# CAMGO.net
KiCad netlist of a schematic drawn in EAGLE
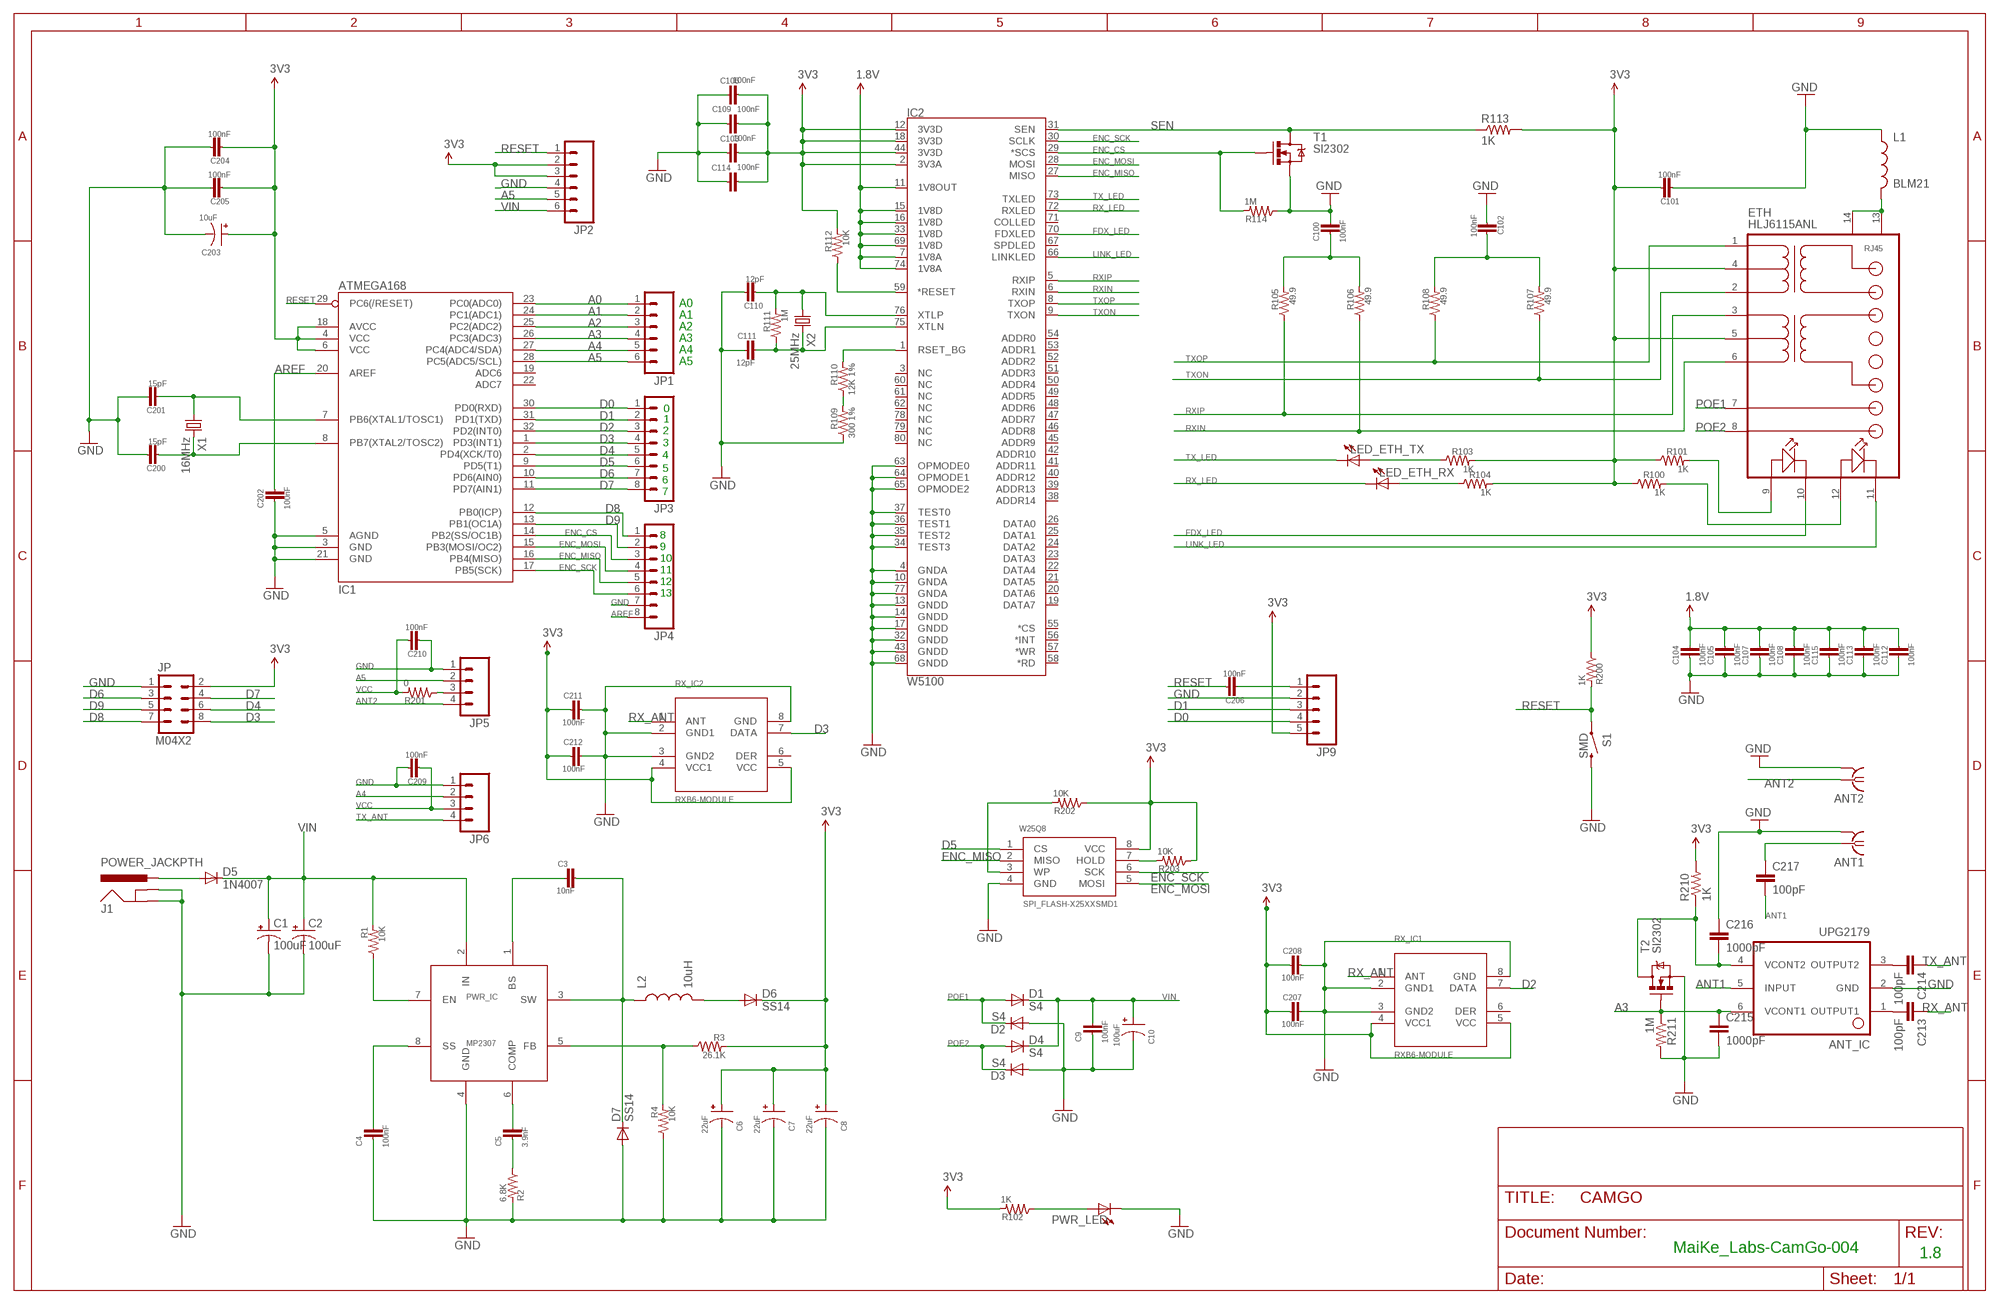
[diagram p0: schematic, sheet 1]

(export (version "E")
  (design (tool "Eeschema 10.0.6"))
  (components
    (comp (ref "ANT1")
      (value "SMA--KE")
      (footprint "eagle-import:SMA-KE")
      (libsource (lib "eagle-import") (part "SMA--KE"))
    )
    (comp (ref "ANT2")
      (value "SMA--KE")
      (footprint "eagle-import:SMA-KE")
      (libsource (lib "eagle-import") (part "SMA--KE"))
    )
    (comp (ref "ANT_IC")
      (value "UPG2179")
      (footprint "eagle-import:SOT363")
      (libsource (lib "eagle-import") (part "UPG2179"))
    )
    (comp (ref "C1")
      (value "100uF")
      (footprint "eagle-import:NIPPON_F80")
      (libsource (lib "eagle-import") (part "CAP_POLF80"))
    )
    (comp (ref "C2")
      (value "100uF")
      (footprint "eagle-import:NIPPON_F80")
      (libsource (lib "eagle-import") (part "CAP_POLF80"))
    )
    (comp (ref "C3")
      (value "10nF")
      (footprint "eagle-import:0603-CAP")
      (libsource (lib "eagle-import") (part "digital-toy_CAP0603-CAP"))
    )
    (comp (ref "C4")
      (value "100nF")
      (footprint "eagle-import:0603-CAP")
      (libsource (lib "eagle-import") (part "digital-toy_CAP0603-CAP"))
    )
    (comp (ref "C5")
      (value "3.9nF")
      (footprint "eagle-import:0603-CAP")
      (libsource (lib "eagle-import") (part "digital-toy_CAP0603-CAP"))
    )
    (comp (ref "C6")
      (value "22uF")
      (footprint "eagle-import:EIA3216")
      (libsource (lib "eagle-import") (part "digital-toy_CAP_POL1206"))
    )
    (comp (ref "C7")
      (value "22uF")
      (footprint "eagle-import:EIA3216")
      (libsource (lib "eagle-import") (part "digital-toy_CAP_POL1206"))
    )
    (comp (ref "C8")
      (value "22uF")
      (footprint "eagle-import:EIA3216")
      (libsource (lib "eagle-import") (part "digital-toy_CAP_POL1206"))
    )
    (comp (ref "C9")
      (value "100nF")
      (footprint "eagle-import:0603-CAP")
      (libsource (lib "eagle-import") (part "digital-toy_CAP0603-CAP"))
    )
    (comp (ref "C10")
      (value "100uF")
      (footprint "eagle-import:NIPPON_F80")
      (libsource (lib "eagle-import") (part "digital-toy_CAP_POLF80"))
    )
    (comp (ref "C100")
      (value "100nF")
      (footprint "eagle-import:0603-CAP")
      (libsource (lib "eagle-import") (part "digital-toy_CAP0603-CAP"))
    )
    (comp (ref "C101")
      (value "100nF")
      (footprint "eagle-import:0603-CAP")
      (libsource (lib "eagle-import") (part "digital-toy_CAP0603-CAP"))
    )
    (comp (ref "C102")
      (value "100nF")
      (footprint "eagle-import:0603-CAP")
      (libsource (lib "eagle-import") (part "digital-toy_CAP0603-CAP"))
    )
    (comp (ref "C103")
      (value "100nF")
      (footprint "eagle-import:0603-CAP")
      (libsource (lib "eagle-import") (part "digital-toy_CAP0603-CAP"))
    )
    (comp (ref "C104")
      (value "100nF")
      (footprint "eagle-import:0603-CAP")
      (libsource (lib "eagle-import") (part "digital-toy_CAP0603-CAP"))
    )
    (comp (ref "C105")
      (value "100nF")
      (footprint "eagle-import:0603-CAP")
      (libsource (lib "eagle-import") (part "digital-toy_CAP0603-CAP"))
    )
    (comp (ref "C106")
      (value "100nF")
      (footprint "eagle-import:0603-CAP")
      (libsource (lib "eagle-import") (part "digital-toy_CAP0603-CAP"))
    )
    (comp (ref "C107")
      (value "100nF")
      (footprint "eagle-import:0603-CAP")
      (libsource (lib "eagle-import") (part "digital-toy_CAP0603-CAP"))
    )
    (comp (ref "C108")
      (value "100nF")
      (footprint "eagle-import:0603-CAP")
      (libsource (lib "eagle-import") (part "digital-toy_CAP0603-CAP"))
    )
    (comp (ref "C109")
      (value "100nF")
      (footprint "eagle-import:0603-CAP")
      (libsource (lib "eagle-import") (part "digital-toy_CAP0603-CAP"))
    )
    (comp (ref "C110")
      (value "12pF")
      (footprint "eagle-import:0603-CAP")
      (libsource (lib "eagle-import") (part "digital-toy_CAP0603-CAP"))
    )
    (comp (ref "C111")
      (value "12pF")
      (footprint "eagle-import:0603-CAP")
      (libsource (lib "eagle-import") (part "digital-toy_CAP0603-CAP"))
    )
    (comp (ref "C112")
      (value "100nF")
      (footprint "eagle-import:0603-CAP")
      (libsource (lib "eagle-import") (part "digital-toy_CAP0603-CAP"))
    )
    (comp (ref "C113")
      (value "100nF")
      (footprint "eagle-import:0603-CAP")
      (libsource (lib "eagle-import") (part "digital-toy_CAP0603-CAP"))
    )
    (comp (ref "C114")
      (value "100nF")
      (footprint "eagle-import:0603-CAP")
      (libsource (lib "eagle-import") (part "digital-toy_CAP0603-CAP"))
    )
    (comp (ref "C115")
      (value "100nF")
      (footprint "eagle-import:0603-CAP")
      (libsource (lib "eagle-import") (part "digital-toy_CAP0603-CAP"))
    )
    (comp (ref "C200")
      (value "15pF")
      (footprint "eagle-import:0603-CAP")
      (libsource (lib "eagle-import") (part "digital-toy_CAP0603-CAP"))
    )
    (comp (ref "C201")
      (value "15pF")
      (footprint "eagle-import:0603-CAP")
      (libsource (lib "eagle-import") (part "digital-toy_CAP0603-CAP"))
    )
    (comp (ref "C202")
      (value "100nF")
      (footprint "eagle-import:0603-CAP")
      (libsource (lib "eagle-import") (part "digital-toy_CAP0603-CAP"))
    )
    (comp (ref "C203")
      (value "10uF")
      (footprint "eagle-import:EIA3216")
      (libsource (lib "eagle-import") (part "digital-toy_CAP_POL1206"))
    )
    (comp (ref "C204")
      (value "100nF")
      (footprint "eagle-import:0603-CAP")
      (libsource (lib "eagle-import") (part "digital-toy_CAP0603-CAP"))
    )
    (comp (ref "C205")
      (value "100nF")
      (footprint "eagle-import:0603-CAP")
      (libsource (lib "eagle-import") (part "digital-toy_CAP0603-CAP"))
    )
    (comp (ref "C206")
      (value "100nF")
      (footprint "eagle-import:0603-CAP")
      (libsource (lib "eagle-import") (part "digital-toy_CAP0603-CAP"))
    )
    (comp (ref "C207")
      (value "100nF")
      (footprint "eagle-import:0603-CAP")
      (libsource (lib "eagle-import") (part "digital-toy_CAP0603-CAP"))
    )
    (comp (ref "C208")
      (value "100nF")
      (footprint "eagle-import:0603-CAP")
      (libsource (lib "eagle-import") (part "digital-toy_CAP0603-CAP"))
    )
    (comp (ref "C209")
      (value "100nF")
      (footprint "eagle-import:0603-CAP")
      (libsource (lib "eagle-import") (part "digital-toy_CAP0603-CAP"))
    )
    (comp (ref "C210")
      (value "100nF")
      (footprint "eagle-import:0603-CAP")
      (libsource (lib "eagle-import") (part "digital-toy_CAP0603-CAP"))
    )
    (comp (ref "C211")
      (value "100nF")
      (footprint "eagle-import:0603-CAP")
      (libsource (lib "eagle-import") (part "digital-toy_CAP0603-CAP"))
    )
    (comp (ref "C212")
      (value "100nF")
      (footprint "eagle-import:0603-CAP")
      (libsource (lib "eagle-import") (part "digital-toy_CAP0603-CAP"))
    )
    (comp (ref "C213")
      (value "100pF")
      (footprint "eagle-import:0603-CAP")
      (libsource (lib "eagle-import") (part "CAP0603-CAP"))
    )
    (comp (ref "C214")
      (value "100pF")
      (footprint "eagle-import:0603-CAP")
      (libsource (lib "eagle-import") (part "CAP0603-CAP"))
    )
    (comp (ref "C215")
      (value "1000pF")
      (footprint "eagle-import:0603-CAP")
      (libsource (lib "eagle-import") (part "CAP0603-CAP"))
    )
    (comp (ref "C216")
      (value "1000pF")
      (footprint "eagle-import:0603-CAP")
      (libsource (lib "eagle-import") (part "CAP0603-CAP"))
    )
    (comp (ref "C217")
      (value "100pF")
      (footprint "eagle-import:0603-CAP")
      (libsource (lib "eagle-import") (part "CAP0603-CAP"))
    )
    (comp (ref "D1")
      (value "S4")
      (footprint "eagle-import:SOD-323")
      (libsource (lib "eagle-import") (part "ehl_DIODESOD"))
    )
    (comp (ref "D2")
      (value "S4")
      (footprint "eagle-import:SOD-323")
      (libsource (lib "eagle-import") (part "ehl_DIODESOD"))
    )
    (comp (ref "D3")
      (value "S4")
      (footprint "eagle-import:SOD-323")
      (libsource (lib "eagle-import") (part "ehl_DIODESOD"))
    )
    (comp (ref "D4")
      (value "S4")
      (footprint "eagle-import:SOD-323")
      (libsource (lib "eagle-import") (part "ehl_DIODESOD"))
    )
    (comp (ref "D5")
      (value "1N4007")
      (footprint "eagle-import:SMB-DIODE")
      (libsource (lib "eagle-import") (part "DIODESMB"))
    )
    (comp (ref "D6")
      (value "SS14")
      (footprint "eagle-import:SOD-323")
      (libsource (lib "eagle-import") (part "DIODESOD"))
    )
    (comp (ref "D7")
      (value "SS14")
      (footprint "eagle-import:SOD-323")
      (libsource (lib "eagle-import") (part "DIODESOD"))
    )
    (comp (ref "ETH")
      (value "HLJ6115ANL")
      (footprint "eagle-import:HR911105A")
      (libsource (lib "eagle-import") (part "HLJ6115ANL"))
    )
    (comp (ref "IC1")
      (value "ATMEGA168")
      (footprint "eagle-import:TQFP32-08")
      (libsource (lib "eagle-import") (part "ATMEGA168"))
    )
    (comp (ref "IC2")
      (value "W5100")
      (footprint "eagle-import:LQFP-80")
      (libsource (lib "eagle-import") (part "W5100"))
    )
    (comp (ref "J1")
      (value "POWER_JACKPTH")
      (footprint "eagle-import:POWER_JACK_PTH")
      (libsource (lib "eagle-import") (part "POWER_JACKPTH"))
    )
    (comp (ref "JP")
      (value "M04X2")
      (footprint "eagle-import:2X4")
      (libsource (lib "eagle-import") (part "M04X2"))
    )
    (comp (ref "JP1")
      (value "M06SIP")
      (footprint "eagle-import:1X06")
      (libsource (lib "eagle-import") (part "M06SIP"))
    )
    (comp (ref "JP2")
      (value "M06SIP")
      (footprint "eagle-import:1X06")
      (libsource (lib "eagle-import") (part "M06SIP"))
    )
    (comp (ref "JP3")
      (value "M081X08")
      (footprint "eagle-import:1X08")
      (libsource (lib "eagle-import") (part "M081X08"))
    )
    (comp (ref "JP4")
      (value "M081X08")
      (footprint "eagle-import:1X08")
      (libsource (lib "eagle-import") (part "M081X08"))
    )
    (comp (ref "JP5")
      (value "M04PTH")
      (footprint "eagle-import:1X04")
      (libsource (lib "eagle-import") (part "M04PTH"))
    )
    (comp (ref "JP6")
      (value "M04PTH")
      (footprint "eagle-import:1X04")
      (libsource (lib "eagle-import") (part "M04PTH"))
    )
    (comp (ref "JP9")
      (value "M05PTH")
      (footprint "eagle-import:1X05")
      (libsource (lib "eagle-import") (part "M05PTH"))
    )
    (comp (ref "L1")
      (value "BLM21")
      (footprint "eagle-import:0805")
      (libsource (lib "eagle-import") (part "INDUCTOR0805"))
    )
    (comp (ref "L2")
      (value "10uH")
      (footprint "eagle-import:CR54")
      (libsource (lib "eagle-import") (part "INDUCTORCR54"))
    )
    (comp (ref "LED_ETH_RX")
      (value "LED0603")
      (footprint "eagle-import:LED-0603")
      (libsource (lib "eagle-import") (part "LED0603"))
    )
    (comp (ref "LED_ETH_TX")
      (value "LED0603")
      (footprint "eagle-import:LED-0603")
      (libsource (lib "eagle-import") (part "LED0603"))
    )
    (comp (ref "PWR_IC")
      (value "MP2307")
      (footprint "eagle-import:SOIC8")
      (libsource (lib "eagle-import") (part "MP2302"))
    )
    (comp (ref "PWR_LED")
      (value "LED0603")
      (footprint "eagle-import:LED-0603")
      (libsource (lib "eagle-import") (part "LED0603"))
    )
    (comp (ref "R1")
      (value "10K")
      (footprint "eagle-import:0603-RES")
      (libsource (lib "eagle-import") (part "digital-toy_RESISTOR0603-RES"))
    )
    (comp (ref "R2")
      (value "6.8K")
      (footprint "eagle-import:0603-RES")
      (libsource (lib "eagle-import") (part "digital-toy_RESISTOR0603-RES"))
    )
    (comp (ref "R3")
      (value "26.1K")
      (footprint "eagle-import:0603-RES")
      (libsource (lib "eagle-import") (part "digital-toy_RESISTOR0603-RES"))
    )
    (comp (ref "R4")
      (value "10K")
      (footprint "eagle-import:0603-RES")
      (libsource (lib "eagle-import") (part "digital-toy_RESISTOR0603-RES"))
    )
    (comp (ref "R100")
      (value "1K")
      (footprint "eagle-import:0603-RES")
      (libsource (lib "eagle-import") (part "digital-toy_RESISTOR0603-RES"))
    )
    (comp (ref "R101")
      (value "1K")
      (footprint "eagle-import:0603-RES")
      (libsource (lib "eagle-import") (part "digital-toy_RESISTOR0603-RES"))
    )
    (comp (ref "R102")
      (value "1K")
      (footprint "eagle-import:0603-RES")
      (libsource (lib "eagle-import") (part "digital-toy_RESISTOR0603-RES"))
    )
    (comp (ref "R103")
      (value "1K")
      (footprint "eagle-import:0603-RES")
      (libsource (lib "eagle-import") (part "digital-toy_RESISTOR0603-RES"))
    )
    (comp (ref "R104")
      (value "1K")
      (footprint "eagle-import:0603-RES")
      (libsource (lib "eagle-import") (part "digital-toy_RESISTOR0603-RES"))
    )
    (comp (ref "R105")
      (value "49.9")
      (footprint "eagle-import:0603-RES")
      (libsource (lib "eagle-import") (part "digital-toy_RESISTOR0603-RES"))
    )
    (comp (ref "R106")
      (value "49.9")
      (footprint "eagle-import:0603-RES")
      (libsource (lib "eagle-import") (part "digital-toy_RESISTOR0603-RES"))
    )
    (comp (ref "R107")
      (value "49.9")
      (footprint "eagle-import:0603-RES")
      (libsource (lib "eagle-import") (part "digital-toy_RESISTOR0603-RES"))
    )
    (comp (ref "R108")
      (value "49.9")
      (footprint "eagle-import:0603-RES")
      (libsource (lib "eagle-import") (part "digital-toy_RESISTOR0603-RES"))
    )
    (comp (ref "R109")
      (value "300 1%")
      (footprint "eagle-import:0603-RES")
      (libsource (lib "eagle-import") (part "digital-toy_RESISTOR0603-RES"))
    )
    (comp (ref "R110")
      (value "12K 1%")
      (footprint "eagle-import:0603-RES")
      (libsource (lib "eagle-import") (part "digital-toy_RESISTOR0603-RES"))
    )
    (comp (ref "R111")
      (value "1M")
      (footprint "eagle-import:0603-RES")
      (libsource (lib "eagle-import") (part "digital-toy_RESISTOR0603-RES"))
    )
    (comp (ref "R112")
      (value "10K")
      (footprint "eagle-import:0603-RES")
      (libsource (lib "eagle-import") (part "digital-toy_RESISTOR0603-RES"))
    )
    (comp (ref "R113")
      (value "1K")
      (footprint "eagle-import:0603-RES")
      (libsource (lib "eagle-import") (part "RESISTOR0603-RES"))
    )
    (comp (ref "R114")
      (value "1M")
      (footprint "eagle-import:0603-RES")
      (libsource (lib "eagle-import") (part "digital-toy_RESISTOR0603-RES"))
    )
    (comp (ref "R200")
      (value "1K")
      (footprint "eagle-import:0603-RES")
      (libsource (lib "eagle-import") (part "digital-toy_RESISTOR0603-RES"))
    )
    (comp (ref "R201")
      (value "0")
      (footprint "eagle-import:0603-RES")
      (libsource (lib "eagle-import") (part "digital-toy_RESISTOR0603-RES"))
    )
    (comp (ref "R202")
      (value "10K")
      (footprint "eagle-import:0603-RES")
      (libsource (lib "eagle-import") (part "digital-toy_RESISTOR0603-RES"))
    )
    (comp (ref "R203")
      (value "10K")
      (footprint "eagle-import:0603-RES")
      (libsource (lib "eagle-import") (part "digital-toy_RESISTOR0603-RES"))
    )
    (comp (ref "R210")
      (value "1K")
      (footprint "eagle-import:0603-RES")
      (libsource (lib "eagle-import") (part "RESISTOR0603-RES"))
    )
    (comp (ref "R211")
      (value "1M")
      (footprint "eagle-import:0603-RES")
      (libsource (lib "eagle-import") (part "RESISTOR0603-RES"))
    )
    (comp (ref "RX_IC1")
      (value "RXB6-MODULE")
      (footprint "eagle-import:RXB6-MODULE")
      (libsource (lib "eagle-import") (part "RXB6-MODULE"))
    )
    (comp (ref "RX_IC2")
      (value "RXB6-MODULE")
      (footprint "eagle-import:RXB6-MODULE")
      (libsource (lib "eagle-import") (part "RXB6-MODULE"))
    )
    (comp (ref "S1")
      (value "SMD")
      (footprint "eagle-import:TACTILE-SWITCH-1101NE")
      (libsource (lib "eagle-import") (part "SWITCH-MOMENTARY-2-SMD-1101NE"))
    )
    (comp (ref "T1")
      (value "SI2302")
      (footprint "eagle-import:SOT23-3")
      (libsource (lib "eagle-import") (part "-MOSFET-N-SMD"))
    )
    (comp (ref "T2")
      (value "SI2302")
      (footprint "eagle-import:SOT23-3")
      (libsource (lib "eagle-import") (part "-MOSFET-N-SMD"))
    )
    (comp (ref "W25Q8")
      (value "SPI_FLASH-X25XXSMD1")
      (footprint "eagle-import:SO08-EIAJ")
      (libsource (lib "eagle-import") (part "SPI_FLASH-X25XXSMD1"))
    )
    (comp (ref "X1")
      (value "16MHz")
      (footprint "eagle-import:HC49US")
      (libsource (lib "eagle-import") (part "CRYSTALHC49US"))
    )
    (comp (ref "X2")
      (value "25MHz")
      (footprint "eagle-import:HC49US")
      (libsource (lib "eagle-import") (part "CRYSTALHC49US"))
    )
  )
  (nets
    (net (code "1") (name "/A0") (class "Default")
      (node (ref "IC1") (pin "23") (pinfunction "PC0(ADC0)_23") (pintype "bidirectional"))
      (node (ref "JP1") (pin "1") (pinfunction "1_1") (pintype "passive"))
    )
    (net (code "2") (name "/A1") (class "Default")
      (node (ref "IC1") (pin "24") (pinfunction "PC1(ADC1)_24") (pintype "bidirectional"))
      (node (ref "JP1") (pin "2") (pinfunction "2_2") (pintype "passive"))
    )
    (net (code "3") (name "/A2") (class "Default")
      (node (ref "IC1") (pin "25") (pinfunction "PC2(ADC2)_25") (pintype "bidirectional"))
      (node (ref "JP1") (pin "3") (pinfunction "3_3") (pintype "passive"))
    )
    (net (code "4") (name "/A3") (class "Default")
      (node (ref "ANT_IC") (pin "6") (pinfunction "VCONT1_6") (pintype "bidirectional"))
      (node (ref "C215") (pin "1") (pinfunction "1_1") (pintype "passive"))
      (node (ref "IC1") (pin "26") (pinfunction "PC3(ADC3)_26") (pintype "bidirectional"))
      (node (ref "JP1") (pin "4") (pinfunction "4_4") (pintype "passive"))
      (node (ref "R211") (pin "1") (pinfunction "1_1") (pintype "passive"))
      (node (ref "T2") (pin "1") (pinfunction "G_1") (pintype "passive"))
    )
    (net (code "5") (name "/A4") (class "Default")
      (node (ref "IC1") (pin "27") (pinfunction "PC4(ADC4/SDA)_27") (pintype "bidirectional"))
      (node (ref "JP1") (pin "5") (pinfunction "5_5") (pintype "passive"))
      (node (ref "JP6") (pin "2") (pinfunction "2_2") (pintype "passive"))
    )
    (net (code "6") (name "/A5") (class "Default")
      (node (ref "IC1") (pin "28") (pinfunction "PC5(ADC5/SCL)_28") (pintype "bidirectional"))
      (node (ref "JP1") (pin "6") (pinfunction "6_6") (pintype "passive"))
      (node (ref "JP2") (pin "5") (pinfunction "5_5") (pintype "passive"))
      (node (ref "JP5") (pin "2") (pinfunction "2_2") (pintype "passive"))
    )
    (net (code "7") (name "/ANT1") (class "Default")
      (node (ref "ANT_IC") (pin "5") (pinfunction "INPUT_5") (pintype "bidirectional"))
      (node (ref "C217") (pin "2") (pinfunction "2_2") (pintype "passive"))
    )
    (net (code "8") (name "/ANT2") (class "Default")
      (node (ref "ANT2") (pin "1") (pinfunction "1_1") (pintype "passive"))
      (node (ref "JP5") (pin "4") (pinfunction "4_4") (pintype "passive"))
    )
    (net (code "9") (name "/AREF") (class "Default")
      (node (ref "C202") (pin "1") (pinfunction "1_1") (pintype "passive"))
      (node (ref "IC1") (pin "20") (pinfunction "AREF_20") (pintype "bidirectional"))
      (node (ref "JP4") (pin "8") (pinfunction "8_8") (pintype "passive"))
    )
    (net (code "10") (name "/D0") (class "Default")
      (node (ref "IC1") (pin "30") (pinfunction "PD0(RXD)_30") (pintype "bidirectional"))
      (node (ref "JP3") (pin "1") (pinfunction "1_1") (pintype "passive"))
      (node (ref "JP9") (pin "4") (pinfunction "4_4") (pintype "passive"))
    )
    (net (code "11") (name "/D1") (class "Default")
      (node (ref "IC1") (pin "31") (pinfunction "PD1(TXD)_31") (pintype "bidirectional"))
      (node (ref "JP3") (pin "2") (pinfunction "2_2") (pintype "passive"))
      (node (ref "JP9") (pin "3") (pinfunction "3_3") (pintype "passive"))
    )
    (net (code "12") (name "/D2") (class "Default")
      (node (ref "IC1") (pin "32") (pinfunction "PD2(INT0)_32") (pintype "bidirectional"))
      (node (ref "JP3") (pin "3") (pinfunction "3_3") (pintype "passive"))
      (node (ref "RX_IC1") (pin "7") (pinfunction "DATA_7") (pintype "bidirectional"))
    )
    (net (code "13") (name "/D3") (class "Default")
      (node (ref "IC1") (pin "1") (pinfunction "PD3(INT1)_1") (pintype "bidirectional"))
      (node (ref "JP") (pin "8") (pinfunction "8_8") (pintype "passive"))
      (node (ref "JP3") (pin "4") (pinfunction "4_4") (pintype "passive"))
      (node (ref "RX_IC2") (pin "7") (pinfunction "DATA_7") (pintype "bidirectional"))
    )
    (net (code "14") (name "/D4") (class "Default")
      (node (ref "IC1") (pin "2") (pinfunction "PD4(XCK/T0)_2") (pintype "bidirectional"))
      (node (ref "JP") (pin "6") (pinfunction "6_6") (pintype "passive"))
      (node (ref "JP3") (pin "5") (pinfunction "5_5") (pintype "passive"))
    )
    (net (code "15") (name "/D5") (class "Default")
      (node (ref "IC1") (pin "9") (pinfunction "PD5(T1)_9") (pintype "bidirectional"))
      (node (ref "JP3") (pin "6") (pinfunction "6_6") (pintype "passive"))
      (node (ref "W25Q8") (pin "1") (pinfunction "CS_1") (pintype "bidirectional"))
    )
    (net (code "16") (name "/D6") (class "Default")
      (node (ref "IC1") (pin "10") (pinfunction "PD6(AIN0)_10") (pintype "bidirectional"))
      (node (ref "JP") (pin "3") (pinfunction "3_3") (pintype "passive"))
      (node (ref "JP3") (pin "7") (pinfunction "7_7") (pintype "passive"))
    )
    (net (code "17") (name "/D7") (class "Default")
      (node (ref "IC1") (pin "11") (pinfunction "PD7(AIN1)_11") (pintype "bidirectional"))
      (node (ref "JP") (pin "4") (pinfunction "4_4") (pintype "passive"))
      (node (ref "JP3") (pin "8") (pinfunction "8_8") (pintype "passive"))
    )
    (net (code "18") (name "/D8") (class "Default")
      (node (ref "IC1") (pin "12") (pinfunction "PB0(ICP)_12") (pintype "bidirectional"))
      (node (ref "JP") (pin "7") (pinfunction "7_7") (pintype "passive"))
      (node (ref "JP4") (pin "1") (pinfunction "1_1") (pintype "passive"))
    )
    (net (code "19") (name "/D9") (class "Default")
      (node (ref "IC1") (pin "13") (pinfunction "PB1(OC1A)_13") (pintype "bidirectional"))
      (node (ref "JP") (pin "5") (pinfunction "5_5") (pintype "passive"))
      (node (ref "JP4") (pin "2") (pinfunction "2_2") (pintype "passive"))
    )
    (net (code "20") (name "/ENC_CS") (class "Default")
      (node (ref "IC1") (pin "14") (pinfunction "PB2(SS/OC1B)_14") (pintype "bidirectional"))
      (node (ref "IC2") (pin "29") (pinfunction "*SCS_29") (pintype "bidirectional"))
      (node (ref "JP4") (pin "3") (pinfunction "3_3") (pintype "passive"))
      (node (ref "R114") (pin "2") (pinfunction "2_2") (pintype "passive"))
      (node (ref "T1") (pin "1") (pinfunction "G_1") (pintype "passive"))
    )
    (net (code "21") (name "/ENC_MISO") (class "Default")
      (node (ref "IC1") (pin "16") (pinfunction "PB4(MISO)_16") (pintype "bidirectional"))
      (node (ref "IC2") (pin "27") (pinfunction "MISO_27") (pintype "bidirectional"))
      (node (ref "JP4") (pin "5") (pinfunction "5_5") (pintype "passive"))
      (node (ref "W25Q8") (pin "2") (pinfunction "MISO_2") (pintype "bidirectional"))
    )
    (net (code "22") (name "/ENC_MOSI") (class "Default")
      (node (ref "IC1") (pin "15") (pinfunction "PB3(MOSI/OC2)_15") (pintype "bidirectional"))
      (node (ref "IC2") (pin "28") (pinfunction "MOSI_28") (pintype "bidirectional"))
      (node (ref "JP4") (pin "4") (pinfunction "4_4") (pintype "passive"))
      (node (ref "W25Q8") (pin "5") (pinfunction "MOSI_5") (pintype "bidirectional"))
    )
    (net (code "23") (name "/ENC_SCK") (class "Default")
      (node (ref "IC1") (pin "17") (pinfunction "PB5(SCK)_17") (pintype "bidirectional"))
      (node (ref "IC2") (pin "30") (pinfunction "SCLK_30") (pintype "bidirectional"))
      (node (ref "JP4") (pin "6") (pinfunction "6_6") (pintype "passive"))
      (node (ref "W25Q8") (pin "6") (pinfunction "SCK_6") (pintype "bidirectional"))
    )
    (net (code "24") (name "/FDX_LED") (class "Default")
      (node (ref "ETH") (pin "10") (pinfunction "10_10") (pintype "bidirectional"))
      (node (ref "IC2") (pin "70") (pinfunction "FDXLED_70") (pintype "bidirectional"))
    )
    (net (code "25") (name "/LINK_LED") (class "Default")
      (node (ref "ETH") (pin "11") (pinfunction "11_11") (pintype "bidirectional"))
      (node (ref "IC2") (pin "66") (pinfunction "LINKLED_66") (pintype "bidirectional"))
    )
    (net (code "26") (name "/POE1") (class "Default")
      (node (ref "D1") (pin "2") (pinfunction "A_2") (pintype "passive"))
      (node (ref "D2") (pin "1") (pinfunction "C_1") (pintype "passive"))
      (node (ref "ETH") (pin "7") (pinfunction "7_7") (pintype "bidirectional"))
    )
    (net (code "27") (name "/POE2") (class "Default")
      (node (ref "D3") (pin "1") (pinfunction "C_1") (pintype "passive"))
      (node (ref "D4") (pin "2") (pinfunction "A_2") (pintype "passive"))
      (node (ref "ETH") (pin "8") (pinfunction "8_8") (pintype "bidirectional"))
    )
    (net (code "28") (name "/RESET") (class "Default")
      (node (ref "C206") (pin "1") (pinfunction "1_1") (pintype "passive"))
      (node (ref "IC1") (pin "29") (pinfunction "PC6(/RESET)_29") (pintype "bidirectional"))
      (node (ref "IC2") (pin "59") (pinfunction "*RESET_59") (pintype "bidirectional"))
      (node (ref "JP2") (pin "1") (pinfunction "1_1") (pintype "passive"))
      (node (ref "R112") (pin "1") (pinfunction "1_1") (pintype "passive"))
      (node (ref "R200") (pin "2") (pinfunction "2_2") (pintype "passive"))
      (node (ref "S1") (pin "P$1") (pinfunction "1_P$1") (pintype "passive"))
    )
    (net (code "29") (name "/RXIN") (class "Default")
      (node (ref "ETH") (pin "6") (pinfunction "6_6") (pintype "bidirectional"))
      (node (ref "IC2") (pin "6") (pinfunction "RXIN_6") (pintype "bidirectional"))
      (node (ref "R106") (pin "1") (pinfunction "1_1") (pintype "passive"))
    )
    (net (code "30") (name "/RXIP") (class "Default")
      (node (ref "ETH") (pin "3") (pinfunction "3_3") (pintype "bidirectional"))
      (node (ref "IC2") (pin "5") (pinfunction "RXIP_5") (pintype "bidirectional"))
      (node (ref "R105") (pin "1") (pinfunction "1_1") (pintype "passive"))
    )
    (net (code "31") (name "/RX_ANT") (class "Default")
      (node (ref "C213") (pin "1") (pinfunction "1_1") (pintype "passive"))
      (node (ref "RX_IC1") (pin "1") (pinfunction "ANT_1") (pintype "bidirectional"))
      (node (ref "RX_IC2") (pin "1") (pinfunction "ANT_1") (pintype "bidirectional"))
    )
    (net (code "32") (name "/RX_LED") (class "Default")
      (node (ref "IC2") (pin "72") (pinfunction "RXLED_72") (pintype "bidirectional"))
      (node (ref "LED_ETH_RX") (pin "C") (pinfunction "C_C") (pintype "passive"))
    )
    (net (code "33") (name "/SEN") (class "Default")
      (node (ref "IC2") (pin "31") (pinfunction "SEN_31") (pintype "bidirectional"))
      (node (ref "R113") (pin "1") (pinfunction "1_1") (pintype "passive"))
      (node (ref "T1") (pin "3") (pinfunction "D_3") (pintype "passive"))
    )
    (net (code "34") (name "/TXON") (class "Default")
      (node (ref "ETH") (pin "2") (pinfunction "2_2") (pintype "bidirectional"))
      (node (ref "IC2") (pin "9") (pinfunction "TXON_9") (pintype "bidirectional"))
      (node (ref "R107") (pin "1") (pinfunction "1_1") (pintype "passive"))
    )
    (net (code "35") (name "/TXOP") (class "Default")
      (node (ref "ETH") (pin "1") (pinfunction "1_1") (pintype "bidirectional"))
      (node (ref "IC2") (pin "8") (pinfunction "TXOP_8") (pintype "bidirectional"))
      (node (ref "R108") (pin "1") (pinfunction "1_1") (pintype "passive"))
    )
    (net (code "36") (name "/TX_ANT") (class "Default")
      (node (ref "C214") (pin "1") (pinfunction "1_1") (pintype "passive"))
      (node (ref "JP6") (pin "4") (pinfunction "4_4") (pintype "passive"))
    )
    (net (code "37") (name "/TX_LED") (class "Default")
      (node (ref "IC2") (pin "73") (pinfunction "TXLED_73") (pintype "bidirectional"))
      (node (ref "LED_ETH_TX") (pin "C") (pinfunction "C_C") (pintype "passive"))
    )
    (net (code "38") (name "/VIN") (class "Default")
      (node (ref "C1") (pin "+") (pinfunction "+_+") (pintype "passive"))
      (node (ref "C10") (pin "+") (pinfunction "+_+") (pintype "passive"))
      (node (ref "C2") (pin "+") (pinfunction "+_+") (pintype "passive"))
      (node (ref "C9") (pin "1") (pinfunction "1_1") (pintype "passive"))
      (node (ref "D1") (pin "1") (pinfunction "C_1") (pintype "passive"))
      (node (ref "D4") (pin "1") (pinfunction "C_1") (pintype "passive"))
      (node (ref "D5") (pin "C") (pinfunction "C_C") (pintype "passive"))
      (node (ref "JP2") (pin "6") (pinfunction "6_6") (pintype "passive"))
      (node (ref "PWR_IC") (pin "2") (pinfunction "IN_2") (pintype "bidirectional"))
      (node (ref "R1") (pin "2") (pinfunction "2_2") (pintype "passive"))
    )
    (net (code "39") (name "1.8V") (class "Default")
      (node (ref "C104") (pin "1") (pinfunction "1_1") (pintype "passive"))
      (node (ref "C105") (pin "1") (pinfunction "1_1") (pintype "passive"))
      (node (ref "C107") (pin "1") (pinfunction "1_1") (pintype "passive"))
      (node (ref "C108") (pin "1") (pinfunction "1_1") (pintype "passive"))
      (node (ref "C112") (pin "1") (pinfunction "1_1") (pintype "passive"))
      (node (ref "C113") (pin "1") (pinfunction "1_1") (pintype "passive"))
      (node (ref "C115") (pin "1") (pinfunction "1_1") (pintype "passive"))
      (node (ref "IC2") (pin "11") (pinfunction "1V8OUT_11") (pintype "bidirectional"))
      (node (ref "IC2") (pin "15") (pinfunction "1V8D_15") (pintype "bidirectional"))
      (node (ref "IC2") (pin "16") (pinfunction "1V8D_16") (pintype "bidirectional"))
      (node (ref "IC2") (pin "33") (pinfunction "1V8D_33") (pintype "bidirectional"))
      (node (ref "IC2") (pin "69") (pinfunction "1V8D_69") (pintype "bidirectional"))
      (node (ref "IC2") (pin "7") (pinfunction "1V8A_7") (pintype "bidirectional"))
      (node (ref "IC2") (pin "74") (pinfunction "1V8A_74") (pintype "bidirectional"))
    )
    (net (code "40") (name "3V3") (class "Default")
      (node (ref "C101") (pin "1") (pinfunction "1_1") (pintype "passive"))
      (node (ref "C103") (pin "1") (pinfunction "1_1") (pintype "passive"))
      (node (ref "C106") (pin "1") (pinfunction "1_1") (pintype "passive"))
      (node (ref "C109") (pin "2") (pinfunction "2_2") (pintype "passive"))
      (node (ref "C114") (pin "2") (pinfunction "2_2") (pintype "passive"))
      (node (ref "C203") (pin "A") (pinfunction "+_A") (pintype "passive"))
      (node (ref "C204") (pin "2") (pinfunction "2_2") (pintype "passive"))
      (node (ref "C205") (pin "2") (pinfunction "2_2") (pintype "passive"))
      (node (ref "C207") (pin "2") (pinfunction "2_2") (pintype "passive"))
      (node (ref "C208") (pin "2") (pinfunction "2_2") (pintype "passive"))
      (node (ref "C209") (pin "2") (pinfunction "2_2") (pintype "passive"))
      (node (ref "C210") (pin "1") (pinfunction "1_1") (pintype "passive"))
      (node (ref "C211") (pin "2") (pinfunction "2_2") (pintype "passive"))
      (node (ref "C212") (pin "2") (pinfunction "2_2") (pintype "passive"))
      (node (ref "C6") (pin "A") (pinfunction "+_A") (pintype "passive"))
      (node (ref "C7") (pin "A") (pinfunction "+_A") (pintype "passive"))
      (node (ref "C8") (pin "A") (pinfunction "+_A") (pintype "passive"))
      (node (ref "D6") (pin "1") (pinfunction "C_1") (pintype "passive"))
      (node (ref "ETH") (pin "4") (pinfunction "4_4") (pintype "bidirectional"))
      (node (ref "ETH") (pin "5") (pinfunction "5_5") (pintype "bidirectional"))
      (node (ref "IC1") (pin "18") (pinfunction "AVCC_18") (pintype "bidirectional"))
      (node (ref "IC1") (pin "4") (pinfunction "VCC_4") (pintype "bidirectional"))
      (node (ref "IC1") (pin "6") (pinfunction "VCC_6") (pintype "bidirectional"))
      (node (ref "IC2") (pin "12") (pinfunction "3V3D_12") (pintype "bidirectional"))
      (node (ref "IC2") (pin "18") (pinfunction "3V3D_18") (pintype "bidirectional"))
      (node (ref "IC2") (pin "2") (pinfunction "3V3A_2") (pintype "bidirectional"))
      (node (ref "IC2") (pin "44") (pinfunction "3V3D_44") (pintype "bidirectional"))
      (node (ref "JP") (pin "2") (pinfunction "2_2") (pintype "passive"))
      (node (ref "JP2") (pin "2") (pinfunction "2_2") (pintype "passive"))
      (node (ref "JP2") (pin "3") (pinfunction "3_3") (pintype "passive"))
      (node (ref "JP6") (pin "3") (pinfunction "3_3") (pintype "passive"))
      (node (ref "JP9") (pin "5") (pinfunction "5_5") (pintype "passive"))
      (node (ref "R100") (pin "1") (pinfunction "1_1") (pintype "passive"))
      (node (ref "R101") (pin "1") (pinfunction "1_1") (pintype "passive"))
      (node (ref "R102") (pin "2") (pinfunction "2_2") (pintype "passive"))
      (node (ref "R103") (pin "2") (pinfunction "2_2") (pintype "passive"))
      (node (ref "R104") (pin "2") (pinfunction "2_2") (pintype "passive"))
      (node (ref "R112") (pin "2") (pinfunction "2_2") (pintype "passive"))
      (node (ref "R113") (pin "2") (pinfunction "2_2") (pintype "passive"))
      (node (ref "R200") (pin "1") (pinfunction "1_1") (pintype "passive"))
      (node (ref "R201") (pin "2") (pinfunction "2_2") (pintype "passive"))
      (node (ref "R202") (pin "1") (pinfunction "1_1") (pintype "passive"))
      (node (ref "R203") (pin "1") (pinfunction "1_1") (pintype "passive"))
      (node (ref "R210") (pin "2") (pinfunction "2_2") (pintype "passive"))
      (node (ref "R3") (pin "2") (pinfunction "2_2") (pintype "passive"))
      (node (ref "RX_IC1") (pin "4") (pinfunction "VCC1_4") (pintype "bidirectional"))
      (node (ref "RX_IC1") (pin "5") (pinfunction "VCC_5") (pintype "bidirectional"))
      (node (ref "RX_IC2") (pin "4") (pinfunction "VCC1_4") (pintype "bidirectional"))
      (node (ref "RX_IC2") (pin "5") (pinfunction "VCC_5") (pintype "bidirectional"))
      (node (ref "W25Q8") (pin "8") (pinfunction "VCC_8") (pintype "bidirectional"))
    )
    (net (code "41") (name "GND") (class "Default")
      (node (ref "ANT1") (pin "G@1") (pinfunction "GND_G@1") (pintype "power_in"))
      (node (ref "ANT2") (pin "G@1") (pinfunction "GND_G@1") (pintype "power_in"))
      (node (ref "ANT_IC") (pin "2") (pinfunction "GND_2") (pintype "bidirectional"))
      (node (ref "C1") (pin "-") (pinfunction "-_-") (pintype "passive"))
      (node (ref "C10") (pin "-") (pinfunction "-_-") (pintype "passive"))
      (node (ref "C100") (pin "1") (pinfunction "1_1") (pintype "passive"))
      (node (ref "C101") (pin "2") (pinfunction "2_2") (pintype "passive"))
      (node (ref "C102") (pin "2") (pinfunction "2_2") (pintype "passive"))
      (node (ref "C103") (pin "2") (pinfunction "2_2") (pintype "passive"))
      (node (ref "C104") (pin "2") (pinfunction "2_2") (pintype "passive"))
      (node (ref "C105") (pin "2") (pinfunction "2_2") (pintype "passive"))
      (node (ref "C106") (pin "2") (pinfunction "2_2") (pintype "passive"))
      (node (ref "C107") (pin "2") (pinfunction "2_2") (pintype "passive"))
      (node (ref "C108") (pin "2") (pinfunction "2_2") (pintype "passive"))
      (node (ref "C109") (pin "1") (pinfunction "1_1") (pintype "passive"))
      (node (ref "C110") (pin "1") (pinfunction "1_1") (pintype "passive"))
      (node (ref "C111") (pin "2") (pinfunction "2_2") (pintype "passive"))
      (node (ref "C112") (pin "2") (pinfunction "2_2") (pintype "passive"))
      (node (ref "C113") (pin "2") (pinfunction "2_2") (pintype "passive"))
      (node (ref "C114") (pin "1") (pinfunction "1_1") (pintype "passive"))
      (node (ref "C115") (pin "2") (pinfunction "2_2") (pintype "passive"))
      (node (ref "C2") (pin "-") (pinfunction "-_-") (pintype "passive"))
      (node (ref "C200") (pin "1") (pinfunction "1_1") (pintype "passive"))
      (node (ref "C201") (pin "1") (pinfunction "1_1") (pintype "passive"))
      (node (ref "C202") (pin "2") (pinfunction "2_2") (pintype "passive"))
      (node (ref "C203") (pin "C") (pinfunction "-_C") (pintype "passive"))
      (node (ref "C204") (pin "1") (pinfunction "1_1") (pintype "passive"))
      (node (ref "C205") (pin "1") (pinfunction "1_1") (pintype "passive"))
      (node (ref "C207") (pin "1") (pinfunction "1_1") (pintype "passive"))
      (node (ref "C208") (pin "1") (pinfunction "1_1") (pintype "passive"))
      (node (ref "C209") (pin "1") (pinfunction "1_1") (pintype "passive"))
      (node (ref "C210") (pin "2") (pinfunction "2_2") (pintype "passive"))
      (node (ref "C211") (pin "1") (pinfunction "1_1") (pintype "passive"))
      (node (ref "C212") (pin "1") (pinfunction "1_1") (pintype "passive"))
      (node (ref "C215") (pin "2") (pinfunction "2_2") (pintype "passive"))
      (node (ref "C216") (pin "1") (pinfunction "1_1") (pintype "passive"))
      (node (ref "C4") (pin "2") (pinfunction "2_2") (pintype "passive"))
      (node (ref "C6") (pin "C") (pinfunction "-_C") (pintype "passive"))
      (node (ref "C7") (pin "C") (pinfunction "-_C") (pintype "passive"))
      (node (ref "C8") (pin "C") (pinfunction "-_C") (pintype "passive"))
      (node (ref "C9") (pin "2") (pinfunction "2_2") (pintype "passive"))
      (node (ref "D2") (pin "2") (pinfunction "A_2") (pintype "passive"))
      (node (ref "D3") (pin "2") (pinfunction "A_2") (pintype "passive"))
      (node (ref "D7") (pin "2") (pinfunction "A_2") (pintype "passive"))
      (node (ref "IC1") (pin "21") (pinfunction "GND_21") (pintype "bidirectional"))
      (node (ref "IC1") (pin "3") (pinfunction "GND_3") (pintype "bidirectional"))
      (node (ref "IC1") (pin "5") (pinfunction "AGND_5") (pintype "bidirectional"))
      (node (ref "IC2") (pin "10") (pinfunction "GNDA_10") (pintype "bidirectional"))
      (node (ref "IC2") (pin "13") (pinfunction "GNDD_13") (pintype "bidirectional"))
      (node (ref "IC2") (pin "14") (pinfunction "GNDD_14") (pintype "bidirectional"))
      (node (ref "IC2") (pin "17") (pinfunction "GNDD_17") (pintype "bidirectional"))
      (node (ref "IC2") (pin "32") (pinfunction "GNDD_32") (pintype "bidirectional"))
      (node (ref "IC2") (pin "34") (pinfunction "TEST3_34") (pintype "bidirectional"))
      (node (ref "IC2") (pin "35") (pinfunction "TEST2_35") (pintype "bidirectional"))
      (node (ref "IC2") (pin "36") (pinfunction "TEST1_36") (pintype "bidirectional"))
      (node (ref "IC2") (pin "37") (pinfunction "TEST0_37") (pintype "bidirectional"))
      (node (ref "IC2") (pin "4") (pinfunction "GNDA_4") (pintype "bidirectional"))
      (node (ref "IC2") (pin "43") (pinfunction "GNDD_43") (pintype "bidirectional"))
      (node (ref "IC2") (pin "63") (pinfunction "OPMODE0_63") (pintype "bidirectional"))
      (node (ref "IC2") (pin "64") (pinfunction "OPMODE1_64") (pintype "bidirectional"))
      (node (ref "IC2") (pin "65") (pinfunction "OPMODE2_65") (pintype "bidirectional"))
      (node (ref "IC2") (pin "68") (pinfunction "GNDD_68") (pintype "bidirectional"))
      (node (ref "IC2") (pin "77") (pinfunction "GNDA_77") (pintype "bidirectional"))
      (node (ref "J1") (pin "GND") (pinfunction "GND_GND") (pintype "bidirectional"))
      (node (ref "J1") (pin "GNDBREAK") (pinfunction "GNDBREAK_GNDBREAK") (pintype "bidirectional"))
      (node (ref "JP") (pin "1") (pinfunction "1_1") (pintype "passive"))
      (node (ref "JP2") (pin "4") (pinfunction "4_4") (pintype "passive"))
      (node (ref "JP4") (pin "7") (pinfunction "7_7") (pintype "passive"))
      (node (ref "JP5") (pin "1") (pinfunction "1_1") (pintype "passive"))
      (node (ref "JP6") (pin "1") (pinfunction "1_1") (pintype "passive"))
      (node (ref "JP9") (pin "2") (pinfunction "2_2") (pintype "passive"))
      (node (ref "L1") (pin "1") (pinfunction "1_1") (pintype "passive"))
      (node (ref "PWR_IC") (pin "4") (pinfunction "GND_4") (pintype "bidirectional"))
      (node (ref "PWR_LED") (pin "C") (pinfunction "C_C") (pintype "passive"))
      (node (ref "R109") (pin "1") (pinfunction "1_1") (pintype "passive"))
      (node (ref "R114") (pin "1") (pinfunction "1_1") (pintype "passive"))
      (node (ref "R2") (pin "2") (pinfunction "2_2") (pintype "passive"))
      (node (ref "R211") (pin "2") (pinfunction "2_2") (pintype "passive"))
      (node (ref "R4") (pin "1") (pinfunction "1_1") (pintype "passive"))
      (node (ref "RX_IC1") (pin "2") (pinfunction "GND1_2") (pintype "bidirectional"))
      (node (ref "RX_IC1") (pin "3") (pinfunction "GND2_3") (pintype "bidirectional"))
      (node (ref "RX_IC1") (pin "8") (pinfunction "GND_8") (pintype "bidirectional"))
      (node (ref "RX_IC2") (pin "2") (pinfunction "GND1_2") (pintype "bidirectional"))
      (node (ref "RX_IC2") (pin "3") (pinfunction "GND2_3") (pintype "bidirectional"))
      (node (ref "RX_IC2") (pin "8") (pinfunction "GND_8") (pintype "bidirectional"))
      (node (ref "S1") (pin "P$2") (pinfunction "2_P$2") (pintype "passive"))
      (node (ref "T1") (pin "2") (pinfunction "S_2") (pintype "passive"))
      (node (ref "T2") (pin "2") (pinfunction "S_2") (pintype "passive"))
      (node (ref "W25Q8") (pin "4") (pinfunction "GND_4") (pintype "bidirectional"))
    )
    (net (code "42") (name "Net-(ANT1-Pad1)") (class "Default")
      (node (ref "ANT1") (pin "1") (pinfunction "1_1") (pintype "passive"))
      (node (ref "C217") (pin "1") (pinfunction "1_1") (pintype "passive"))
    )
    (net (code "43") (name "Net-(ANT_IC-OUTPUT1)") (class "Default")
      (node (ref "ANT_IC") (pin "1") (pinfunction "OUTPUT1_1") (pintype "bidirectional"))
      (node (ref "C213") (pin "2") (pinfunction "2_2") (pintype "passive"))
    )
    (net (code "44") (name "Net-(ANT_IC-OUTPUT2)") (class "Default")
      (node (ref "ANT_IC") (pin "3") (pinfunction "OUTPUT2_3") (pintype "bidirectional"))
      (node (ref "C214") (pin "2") (pinfunction "2_2") (pintype "passive"))
    )
    (net (code "45") (name "Net-(ANT_IC-VCONT2)") (class "Default")
      (node (ref "ANT_IC") (pin "4") (pinfunction "VCONT2_4") (pintype "bidirectional"))
      (node (ref "C216") (pin "2") (pinfunction "2_2") (pintype "passive"))
      (node (ref "R210") (pin "1") (pinfunction "1_1") (pintype "passive"))
      (node (ref "T2") (pin "3") (pinfunction "D_3") (pintype "passive"))
    )
    (net (code "46") (name "Net-(C5-Pad2)") (class "Default")
      (node (ref "C5") (pin "2") (pinfunction "2_2") (pintype "passive"))
      (node (ref "R2") (pin "1") (pinfunction "1_1") (pintype "passive"))
    )
    (net (code "47") (name "Net-(C100-Pad2)") (class "Default")
      (node (ref "C100") (pin "2") (pinfunction "2_2") (pintype "passive"))
      (node (ref "R105") (pin "2") (pinfunction "2_2") (pintype "passive"))
      (node (ref "R106") (pin "2") (pinfunction "2_2") (pintype "passive"))
    )
    (net (code "48") (name "Net-(C102-Pad1)") (class "Default")
      (node (ref "C102") (pin "1") (pinfunction "1_1") (pintype "passive"))
      (node (ref "R107") (pin "2") (pinfunction "2_2") (pintype "passive"))
      (node (ref "R108") (pin "2") (pinfunction "2_2") (pintype "passive"))
    )
    (net (code "49") (name "Net-(C206-Pad2)") (class "Default")
      (node (ref "C206") (pin "2") (pinfunction "2_2") (pintype "passive"))
      (node (ref "JP9") (pin "1") (pinfunction "1_1") (pintype "passive"))
    )
    (net (code "50") (name "Net-(D5-PadA)") (class "Default")
      (node (ref "D5") (pin "A") (pinfunction "A_A") (pintype "passive"))
      (node (ref "J1") (pin "PWR") (pinfunction "PWR_PWR") (pintype "bidirectional"))
    )
    (net (code "51") (name "Net-(D6-A)") (class "Default")
      (node (ref "D6") (pin "2") (pinfunction "A_2") (pintype "passive"))
      (node (ref "L2") (pin "P$2") (pinfunction "2_P$2") (pintype "passive"))
    )
    (net (code "52") (name "Net-(D7-C)") (class "Default")
      (node (ref "C3") (pin "1") (pinfunction "1_1") (pintype "passive"))
      (node (ref "D7") (pin "1") (pinfunction "C_1") (pintype "passive"))
      (node (ref "L2") (pin "P$1") (pinfunction "1_P$1") (pintype "passive"))
      (node (ref "PWR_IC") (pin "3") (pinfunction "SW_3") (pintype "bidirectional"))
    )
    (net (code "53") (name "Net-(ETH-Pad9)") (class "Default")
      (node (ref "ETH") (pin "9") (pinfunction "9_9") (pintype "bidirectional"))
      (node (ref "R101") (pin "2") (pinfunction "2_2") (pintype "passive"))
    )
    (net (code "54") (name "Net-(ETH-Pad12)") (class "Default")
      (node (ref "ETH") (pin "12") (pinfunction "12_12") (pintype "bidirectional"))
      (node (ref "R100") (pin "2") (pinfunction "2_2") (pintype "passive"))
    )
    (net (code "55") (name "Net-(ETH-Pad13)") (class "Default")
      (node (ref "ETH") (pin "13") (pinfunction "13_13") (pintype "bidirectional"))
      (node (ref "ETH") (pin "14") (pinfunction "14_14") (pintype "bidirectional"))
      (node (ref "L1") (pin "2") (pinfunction "2_2") (pintype "passive"))
    )
    (net (code "56") (name "Net-(IC1-PB6(XTAL1{slash}TOSC1))") (class "Default")
      (node (ref "C201") (pin "2") (pinfunction "2_2") (pintype "passive"))
      (node (ref "IC1") (pin "7") (pinfunction "PB6(XTAL1/TOSC1)_7") (pintype "bidirectional"))
      (node (ref "X1") (pin "1") (pinfunction "1_1") (pintype "passive"))
    )
    (net (code "57") (name "Net-(IC1-PB7(XTAL2{slash}TOSC2))") (class "Default")
      (node (ref "C200") (pin "2") (pinfunction "2_2") (pintype "passive"))
      (node (ref "IC1") (pin "8") (pinfunction "PB7(XTAL2/TOSC2)_8") (pintype "bidirectional"))
      (node (ref "X1") (pin "2") (pinfunction "2_2") (pintype "passive"))
    )
    (net (code "58") (name "Net-(IC2-RSET_BG)") (class "Default")
      (node (ref "IC2") (pin "1") (pinfunction "RSET_BG_1") (pintype "bidirectional"))
      (node (ref "R110") (pin "2") (pinfunction "2_2") (pintype "passive"))
    )
    (net (code "59") (name "Net-(IC2-XTLN)") (class "Default")
      (node (ref "C111") (pin "1") (pinfunction "1_1") (pintype "passive"))
      (node (ref "IC2") (pin "75") (pinfunction "XTLN_75") (pintype "bidirectional"))
      (node (ref "R111") (pin "1") (pinfunction "1_1") (pintype "passive"))
      (node (ref "X2") (pin "2") (pinfunction "2_2") (pintype "passive"))
    )
    (net (code "60") (name "Net-(IC2-XTLP)") (class "Default")
      (node (ref "C110") (pin "2") (pinfunction "2_2") (pintype "passive"))
      (node (ref "IC2") (pin "76") (pinfunction "XTLP_76") (pintype "bidirectional"))
      (node (ref "R111") (pin "2") (pinfunction "2_2") (pintype "passive"))
      (node (ref "X2") (pin "1") (pinfunction "1_1") (pintype "passive"))
    )
    (net (code "61") (name "Net-(JP5-Pad3)") (class "Default")
      (node (ref "JP5") (pin "3") (pinfunction "3_3") (pintype "passive"))
      (node (ref "R201") (pin "1") (pinfunction "1_1") (pintype "passive"))
    )
    (net (code "62") (name "Net-(LED_ETH_RX-PadA)") (class "Default")
      (node (ref "LED_ETH_RX") (pin "A") (pinfunction "A_A") (pintype "passive"))
      (node (ref "R104") (pin "1") (pinfunction "1_1") (pintype "passive"))
    )
    (net (code "63") (name "Net-(LED_ETH_TX-PadA)") (class "Default")
      (node (ref "LED_ETH_TX") (pin "A") (pinfunction "A_A") (pintype "passive"))
      (node (ref "R103") (pin "1") (pinfunction "1_1") (pintype "passive"))
    )
    (net (code "64") (name "Net-(PWR_IC-BS)") (class "Default")
      (node (ref "C3") (pin "2") (pinfunction "2_2") (pintype "passive"))
      (node (ref "PWR_IC") (pin "1") (pinfunction "BS_1") (pintype "bidirectional"))
    )
    (net (code "65") (name "Net-(PWR_IC-COMP)") (class "Default")
      (node (ref "C5") (pin "1") (pinfunction "1_1") (pintype "passive"))
      (node (ref "PWR_IC") (pin "6") (pinfunction "COMP_6") (pintype "bidirectional"))
    )
    (net (code "66") (name "Net-(PWR_IC-EN)") (class "Default")
      (node (ref "PWR_IC") (pin "7") (pinfunction "EN_7") (pintype "bidirectional"))
      (node (ref "R1") (pin "1") (pinfunction "1_1") (pintype "passive"))
    )
    (net (code "67") (name "Net-(PWR_IC-FB)") (class "Default")
      (node (ref "PWR_IC") (pin "5") (pinfunction "FB_5") (pintype "bidirectional"))
      (node (ref "R3") (pin "1") (pinfunction "1_1") (pintype "passive"))
      (node (ref "R4") (pin "2") (pinfunction "2_2") (pintype "passive"))
    )
    (net (code "68") (name "Net-(PWR_IC-SS)") (class "Default")
      (node (ref "C4") (pin "1") (pinfunction "1_1") (pintype "passive"))
      (node (ref "PWR_IC") (pin "8") (pinfunction "SS_8") (pintype "bidirectional"))
    )
    (net (code "69") (name "Net-(PWR_LED-PadA)") (class "Default")
      (node (ref "PWR_LED") (pin "A") (pinfunction "A_A") (pintype "passive"))
      (node (ref "R102") (pin "1") (pinfunction "1_1") (pintype "passive"))
    )
    (net (code "70") (name "Net-(R109-Pad2)") (class "Default")
      (node (ref "R109") (pin "2") (pinfunction "2_2") (pintype "passive"))
      (node (ref "R110") (pin "1") (pinfunction "1_1") (pintype "passive"))
    )
    (net (code "71") (name "Net-(W25Q8-HOLD)") (class "Default")
      (node (ref "R203") (pin "2") (pinfunction "2_2") (pintype "passive"))
      (node (ref "W25Q8") (pin "7") (pinfunction "HOLD_7") (pintype "bidirectional"))
    )
    (net (code "72") (name "Net-(W25Q8-WP)") (class "Default")
      (node (ref "R202") (pin "2") (pinfunction "2_2") (pintype "passive"))
      (node (ref "W25Q8") (pin "3") (pinfunction "WP_3") (pintype "bidirectional"))
    )
    (net (code "73") (name "unconnected-(IC1-ADC6-Pad19)") (class "Default")
      (node (ref "IC1") (pin "19") (pinfunction "ADC6_19") (pintype "bidirectional"))
    )
    (net (code "74") (name "unconnected-(IC1-ADC7-Pad22)") (class "Default")
      (node (ref "IC1") (pin "22") (pinfunction "ADC7_22") (pintype "bidirectional"))
    )
    (net (code "75") (name "unconnected-(IC2-*CS-Pad55)") (class "Default")
      (node (ref "IC2") (pin "55") (pinfunction "*CS_55") (pintype "bidirectional"))
    )
    (net (code "76") (name "unconnected-(IC2-*INT-Pad56)") (class "Default")
      (node (ref "IC2") (pin "56") (pinfunction "*INT_56") (pintype "bidirectional"))
    )
    (net (code "77") (name "unconnected-(IC2-*RD-Pad58)") (class "Default")
      (node (ref "IC2") (pin "58") (pinfunction "*RD_58") (pintype "bidirectional"))
    )
    (net (code "78") (name "unconnected-(IC2-*WR-Pad57)") (class "Default")
      (node (ref "IC2") (pin "57") (pinfunction "*WR_57") (pintype "bidirectional"))
    )
    (net (code "79") (name "unconnected-(IC2-ADDR0-Pad54)") (class "Default")
      (node (ref "IC2") (pin "54") (pinfunction "ADDR0_54") (pintype "bidirectional"))
    )
    (net (code "80") (name "unconnected-(IC2-ADDR1-Pad53)") (class "Default")
      (node (ref "IC2") (pin "53") (pinfunction "ADDR1_53") (pintype "bidirectional"))
    )
    (net (code "81") (name "unconnected-(IC2-ADDR2-Pad52)") (class "Default")
      (node (ref "IC2") (pin "52") (pinfunction "ADDR2_52") (pintype "bidirectional"))
    )
    (net (code "82") (name "unconnected-(IC2-ADDR3-Pad51)") (class "Default")
      (node (ref "IC2") (pin "51") (pinfunction "ADDR3_51") (pintype "bidirectional"))
    )
    (net (code "83") (name "unconnected-(IC2-ADDR4-Pad50)") (class "Default")
      (node (ref "IC2") (pin "50") (pinfunction "ADDR4_50") (pintype "bidirectional"))
    )
    (net (code "84") (name "unconnected-(IC2-ADDR5-Pad49)") (class "Default")
      (node (ref "IC2") (pin "49") (pinfunction "ADDR5_49") (pintype "bidirectional"))
    )
    (net (code "85") (name "unconnected-(IC2-ADDR6-Pad48)") (class "Default")
      (node (ref "IC2") (pin "48") (pinfunction "ADDR6_48") (pintype "bidirectional"))
    )
    (net (code "86") (name "unconnected-(IC2-ADDR7-Pad47)") (class "Default")
      (node (ref "IC2") (pin "47") (pinfunction "ADDR7_47") (pintype "bidirectional"))
    )
    (net (code "87") (name "unconnected-(IC2-ADDR8-Pad46)") (class "Default")
      (node (ref "IC2") (pin "46") (pinfunction "ADDR8_46") (pintype "bidirectional"))
    )
    (net (code "88") (name "unconnected-(IC2-ADDR9-Pad45)") (class "Default")
      (node (ref "IC2") (pin "45") (pinfunction "ADDR9_45") (pintype "bidirectional"))
    )
    (net (code "89") (name "unconnected-(IC2-ADDR10-Pad42)") (class "Default")
      (node (ref "IC2") (pin "42") (pinfunction "ADDR10_42") (pintype "bidirectional"))
    )
    (net (code "90") (name "unconnected-(IC2-ADDR11-Pad41)") (class "Default")
      (node (ref "IC2") (pin "41") (pinfunction "ADDR11_41") (pintype "bidirectional"))
    )
    (net (code "91") (name "unconnected-(IC2-ADDR12-Pad40)") (class "Default")
      (node (ref "IC2") (pin "40") (pinfunction "ADDR12_40") (pintype "bidirectional"))
    )
    (net (code "92") (name "unconnected-(IC2-ADDR13-Pad39)") (class "Default")
      (node (ref "IC2") (pin "39") (pinfunction "ADDR13_39") (pintype "bidirectional"))
    )
    (net (code "93") (name "unconnected-(IC2-ADDR14-Pad38)") (class "Default")
      (node (ref "IC2") (pin "38") (pinfunction "ADDR14_38") (pintype "bidirectional"))
    )
    (net (code "94") (name "unconnected-(IC2-COLLED-Pad71)") (class "Default")
      (node (ref "IC2") (pin "71") (pinfunction "COLLED_71") (pintype "bidirectional"))
    )
    (net (code "95") (name "unconnected-(IC2-DATA0-Pad26)") (class "Default")
      (node (ref "IC2") (pin "26") (pinfunction "DATA0_26") (pintype "bidirectional"))
    )
    (net (code "96") (name "unconnected-(IC2-DATA1-Pad25)") (class "Default")
      (node (ref "IC2") (pin "25") (pinfunction "DATA1_25") (pintype "bidirectional"))
    )
    (net (code "97") (name "unconnected-(IC2-DATA2-Pad24)") (class "Default")
      (node (ref "IC2") (pin "24") (pinfunction "DATA2_24") (pintype "bidirectional"))
    )
    (net (code "98") (name "unconnected-(IC2-DATA3-Pad23)") (class "Default")
      (node (ref "IC2") (pin "23") (pinfunction "DATA3_23") (pintype "bidirectional"))
    )
    (net (code "99") (name "unconnected-(IC2-DATA4-Pad22)") (class "Default")
      (node (ref "IC2") (pin "22") (pinfunction "DATA4_22") (pintype "bidirectional"))
    )
    (net (code "100") (name "unconnected-(IC2-DATA5-Pad21)") (class "Default")
      (node (ref "IC2") (pin "21") (pinfunction "DATA5_21") (pintype "bidirectional"))
    )
    (net (code "101") (name "unconnected-(IC2-DATA6-Pad20)") (class "Default")
      (node (ref "IC2") (pin "20") (pinfunction "DATA6_20") (pintype "bidirectional"))
    )
    (net (code "102") (name "unconnected-(IC2-DATA7-Pad19)") (class "Default")
      (node (ref "IC2") (pin "19") (pinfunction "DATA7_19") (pintype "bidirectional"))
    )
    (net (code "103") (name "unconnected-(IC2-NC-Pad3)") (class "Default")
      (node (ref "IC2") (pin "3") (pinfunction "NC_3") (pintype "bidirectional"))
    )
    (net (code "104") (name "unconnected-(IC2-NC-Pad60)") (class "Default")
      (node (ref "IC2") (pin "60") (pinfunction "NC_60") (pintype "bidirectional"))
    )
    (net (code "105") (name "unconnected-(IC2-NC-Pad61)") (class "Default")
      (node (ref "IC2") (pin "61") (pinfunction "NC_61") (pintype "bidirectional"))
    )
    (net (code "106") (name "unconnected-(IC2-NC-Pad62)") (class "Default")
      (node (ref "IC2") (pin "62") (pinfunction "NC_62") (pintype "bidirectional"))
    )
    (net (code "107") (name "unconnected-(IC2-NC-Pad78)") (class "Default")
      (node (ref "IC2") (pin "78") (pinfunction "NC_78") (pintype "bidirectional"))
    )
    (net (code "108") (name "unconnected-(IC2-NC-Pad79)") (class "Default")
      (node (ref "IC2") (pin "79") (pinfunction "NC_79") (pintype "bidirectional"))
    )
    (net (code "109") (name "unconnected-(IC2-NC-Pad80)") (class "Default")
      (node (ref "IC2") (pin "80") (pinfunction "NC_80") (pintype "bidirectional"))
    )
    (net (code "110") (name "unconnected-(IC2-SPDLED-Pad67)") (class "Default")
      (node (ref "IC2") (pin "67") (pinfunction "SPDLED_67") (pintype "bidirectional"))
    )
    (net (code "111") (name "unconnected-(RX_IC1-DER-Pad6)") (class "Default")
      (node (ref "RX_IC1") (pin "6") (pinfunction "DER_6") (pintype "bidirectional"))
    )
    (net (code "112") (name "unconnected-(RX_IC2-DER-Pad6)") (class "Default")
      (node (ref "RX_IC2") (pin "6") (pinfunction "DER_6") (pintype "bidirectional"))
    )
  )
)
